# Sensors.net
KiCad netlist of a schematic drawn in Altium Designer
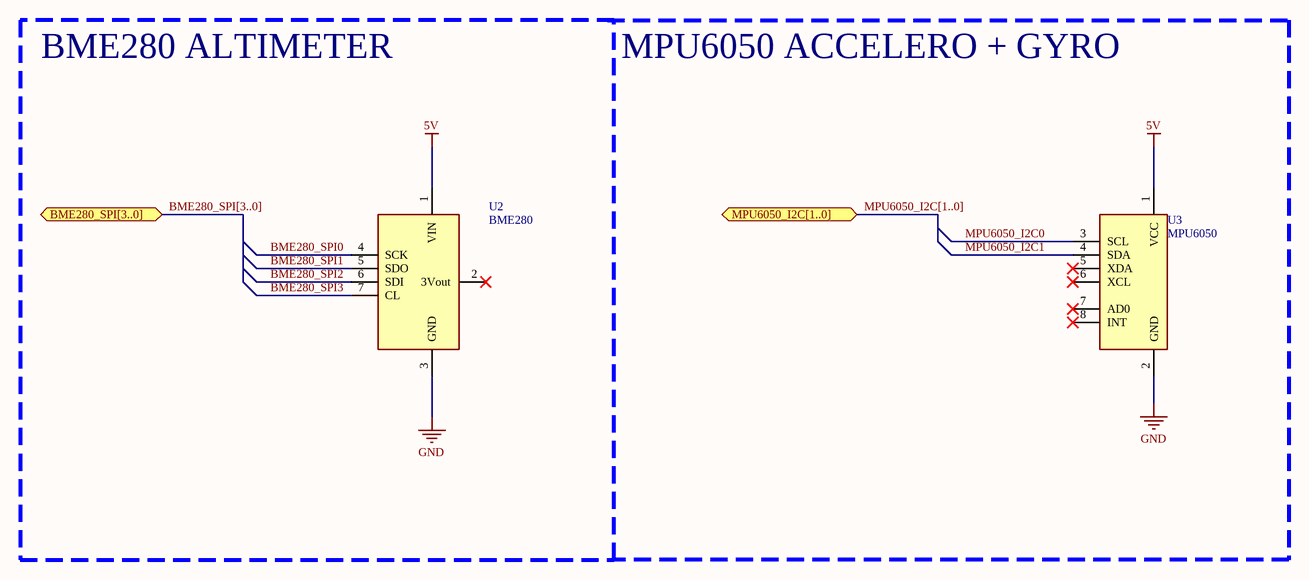
[diagram p0: Sensors.SchDoc]

(export (version "E")
  (design (tool "Eeschema 10.0.6"))
  (components
    (comp (ref "U2") (value "BME280") (footprint "BME280") (libsource (lib "RocketLib") (part "BME280")))
    (comp (ref "U3") (value "MPU6050") (footprint "MPU6050") (libsource (lib "RocketLib") (part "MPU6050")))
  )
  (nets
    (net (code "1") (name "/BME280_SPI0") (class "Default")
      (node (ref "U2") (pin "4") (pinfunction "SCK_4") (pintype "passive"))
    )
    (net (code "2") (name "/BME280_SPI1") (class "Default")
      (node (ref "U2") (pin "5") (pinfunction "SDO_5") (pintype "passive"))
    )
    (net (code "3") (name "/BME280_SPI2") (class "Default")
      (node (ref "U2") (pin "6") (pinfunction "SDI_6") (pintype "passive"))
    )
    (net (code "4") (name "/BME280_SPI3") (class "Default")
      (node (ref "U2") (pin "7") (pinfunction "CL_7") (pintype "passive"))
    )
    (net (code "6") (name "/MPU6050_I2C0") (class "Default")
      (node (ref "U3") (pin "3") (pinfunction "SCL_3") (pintype "passive"))
    )
    (net (code "7") (name "/MPU6050_I2C1") (class "Default")
      (node (ref "U3") (pin "4") (pinfunction "SDA_4") (pintype "passive"))
    )
    (net (code "9") (name "5V") (class "Default")
      (node (ref "U2") (pin "1") (pinfunction "VIN_1") (pintype "passive"))
      (node (ref "U3") (pin "1") (pinfunction "VCC_1") (pintype "passive"))
    )
    (net (code "10") (name "GND") (class "Default")
      (node (ref "U2") (pin "3") (pinfunction "GND_3") (pintype "passive"))
      (node (ref "U3") (pin "2") (pinfunction "GND_2") (pintype "passive"))
    )
    (net (code "11") (name "unconnected-(U2-3Vout-Pad2)") (class "Default")
      (node (ref "U2") (pin "2") (pinfunction "3Vout_2") (pintype "passive+no_connect"))
    )
    (net (code "12") (name "unconnected-(U3-AD0-Pad7)") (class "Default")
      (node (ref "U3") (pin "7") (pinfunction "AD0_7") (pintype "passive+no_connect"))
    )
    (net (code "13") (name "unconnected-(U3-INT-Pad8)") (class "Default")
      (node (ref "U3") (pin "8") (pinfunction "INT_8") (pintype "passive+no_connect"))
    )
    (net (code "14") (name "unconnected-(U3-XCL-Pad6)") (class "Default")
      (node (ref "U3") (pin "6") (pinfunction "XCL_6") (pintype "passive+no_connect"))
    )
    (net (code "15") (name "unconnected-(U3-XDA-Pad5)") (class "Default")
      (node (ref "U3") (pin "5") (pinfunction "XDA_5") (pintype "passive+no_connect"))
    )
  )
)
